# Example_Circuit.net
KiCad netlist of a schematic drawn in EAGLE
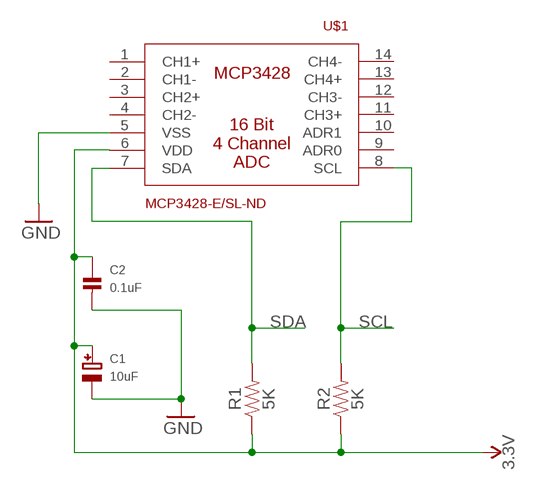
[diagram p0: schematic, sheet 1]

(export (version "E")
  (design (tool "Eeschema 10.0.6"))
  (components
    (comp (ref "C1")
      (value "10uF")
      (footprint "eagle-import:EIA3216-18_A-R")
      (libsource (lib "eagle-import") (part "CAP_TANTALUMA/3216_REFLOW"))
    )
    (comp (ref "C2")
      (value "0.1uF")
      (footprint "eagle-import:0603")
      (libsource (lib "eagle-import") (part "CAP_CERAMIC0603"))
    )
    (comp (ref "R1")
      (value "5K")
      (footprint "eagle-import:0603")
      (libsource (lib "eagle-import") (part "RESISTOR0603"))
    )
    (comp (ref "R2")
      (value "5K")
      (footprint "eagle-import:0603")
      (libsource (lib "eagle-import") (part "RESISTOR0603"))
    )
    (comp (ref "U$1")
      (value "MCP3428-E/SL-ND")
      (footprint "eagle-import:14SOIC")
      (libsource (lib "eagle-import") (part "MCP3428-E/SL-ND"))
    )
  )
  (nets
    (net (code "1") (name "/SCL") (class "Default")
      (node (ref "R2") (pin "2") (pinfunction "2_2") (pintype "passive"))
      (node (ref "U$1") (pin "8") (pinfunction "SCL_8") (pintype "bidirectional"))
    )
    (net (code "2") (name "/SDA") (class "Default")
      (node (ref "R1") (pin "2") (pinfunction "2_2") (pintype "passive"))
      (node (ref "U$1") (pin "7") (pinfunction "SDA_7") (pintype "bidirectional"))
    )
    (net (code "3") (name "3.3V") (class "Default")
      (node (ref "C1") (pin "+") (pinfunction "+_+") (pintype "passive"))
      (node (ref "C2") (pin "1") (pinfunction "P$1_1") (pintype "passive"))
      (node (ref "R1") (pin "1") (pinfunction "1_1") (pintype "passive"))
      (node (ref "R2") (pin "1") (pinfunction "1_1") (pintype "passive"))
      (node (ref "U$1") (pin "6") (pinfunction "VDD_6") (pintype "power_in"))
    )
    (net (code "4") (name "GND") (class "Default")
      (node (ref "C1") (pin "-") (pinfunction "-_-") (pintype "passive"))
      (node (ref "C2") (pin "2") (pinfunction "P$2_2") (pintype "passive"))
      (node (ref "U$1") (pin "5") (pinfunction "VSS_5") (pintype "power_in"))
    )
    (net (code "5") (name "unconnected-(U$1-ADR0-Pad9)") (class "Default")
      (node (ref "U$1") (pin "9") (pinfunction "ADR0_9") (pintype "bidirectional"))
    )
    (net (code "6") (name "unconnected-(U$1-ADR1-Pad10)") (class "Default")
      (node (ref "U$1") (pin "10") (pinfunction "ADR1_10") (pintype "bidirectional"))
    )
    (net (code "7") (name "unconnected-(U$1-CH1+-Pad1)") (class "Default")
      (node (ref "U$1") (pin "1") (pinfunction "CH1+_1") (pintype "bidirectional"))
    )
    (net (code "8") (name "unconnected-(U$1-CH1--Pad2)") (class "Default")
      (node (ref "U$1") (pin "2") (pinfunction "CH1-_2") (pintype "bidirectional"))
    )
    (net (code "9") (name "unconnected-(U$1-CH2+-Pad3)") (class "Default")
      (node (ref "U$1") (pin "3") (pinfunction "CH2+_3") (pintype "bidirectional"))
    )
    (net (code "10") (name "unconnected-(U$1-CH2--Pad4)") (class "Default")
      (node (ref "U$1") (pin "4") (pinfunction "CH2-_4") (pintype "bidirectional"))
    )
    (net (code "11") (name "unconnected-(U$1-CH3+-Pad11)") (class "Default")
      (node (ref "U$1") (pin "11") (pinfunction "CH3+_11") (pintype "bidirectional"))
    )
    (net (code "12") (name "unconnected-(U$1-CH3--Pad12)") (class "Default")
      (node (ref "U$1") (pin "12") (pinfunction "CH3-_12") (pintype "bidirectional"))
    )
    (net (code "13") (name "unconnected-(U$1-CH4+-Pad13)") (class "Default")
      (node (ref "U$1") (pin "13") (pinfunction "CH4+_13") (pintype "bidirectional"))
    )
    (net (code "14") (name "unconnected-(U$1-CH4--Pad14)") (class "Default")
      (node (ref "U$1") (pin "14") (pinfunction "CH4-_14") (pintype "bidirectional"))
    )
  )
)
